# GPS_lure.net
KiCad netlist of a schematic drawn in EAGLE
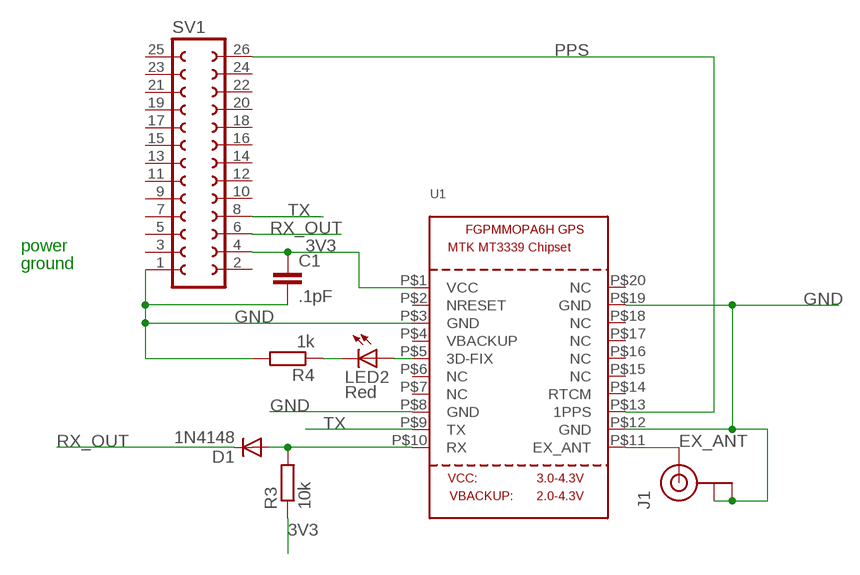
[diagram p0: schematic, sheet 1]

(export (version "E")
  (design (tool "Eeschema 10.0.6"))
  (components
    (comp (ref "C1")
      (value ".1pF")
      (footprint "eagle-import:C0805")
      (libsource (lib "eagle-import") (part "C-EUC0805"))
    )
    (comp (ref "D1")
      (value "1N4148")
      (footprint "eagle-import:SOD123")
      (libsource (lib "eagle-import") (part "DIODE-SOD123"))
    )
    (comp (ref "J1")
      (value "U.FL")
      (footprint "eagle-import:U.FL")
      (libsource (lib "eagle-import") (part "U.FL"))
    )
    (comp (ref "LED2")
      (value "Red")
      (footprint "eagle-import:CHIPLED_1206")
      (libsource (lib "eagle-import") (part "LEDCHIPLED_1206"))
    )
    (comp (ref "R3")
      (value "10k")
      (footprint "eagle-import:M1206")
      (libsource (lib "eagle-import") (part "R-EU_M1206"))
    )
    (comp (ref "R4")
      (value "1k")
      (footprint "eagle-import:M1206")
      (libsource (lib "eagle-import") (part "R-EU_M1206"))
    )
    (comp (ref "SV1")
      (value "FE13-2")
      (footprint "eagle-import:FE13-2")
      (libsource (lib "eagle-import") (part "FE13-2"))
    )
    (comp (ref "U1")
      (value "GPS_FGPMMOPA6H")
      (footprint "eagle-import:FGPMMOPA6H")
      (libsource (lib "eagle-import") (part "GPS_FGPMMOPA6H"))
    )
  )
  (nets
    (net (code "1") (name "/3V3") (class "Default")
      (node (ref "C1") (pin "1") (pinfunction "1_1") (pintype "passive"))
      (node (ref "R3") (pin "1") (pinfunction "1_1") (pintype "passive"))
      (node (ref "SV1") (pin "4") (pinfunction "4_4") (pintype "passive"))
      (node (ref "U1") (pin "P$1") (pinfunction "VCC_P$1") (pintype "bidirectional"))
    )
    (net (code "2") (name "/EX_ANT") (class "Default")
      (node (ref "J1") (pin "P$3") (pinfunction "SIGNAL_P$3") (pintype "bidirectional"))
      (node (ref "U1") (pin "P$11") (pinfunction "EX_ANT_P$11") (pintype "bidirectional"))
    )
    (net (code "3") (name "/GND") (class "Default")
      (node (ref "C1") (pin "2") (pinfunction "2_2") (pintype "passive"))
      (node (ref "J1") (pin "P$1") (pinfunction "GND_P$1") (pintype "bidirectional"))
      (node (ref "J1") (pin "P$2") (pinfunction "GND_P$2") (pintype "bidirectional"))
      (node (ref "R4") (pin "2") (pinfunction "2_2") (pintype "passive"))
      (node (ref "SV1") (pin "1") (pinfunction "1_1") (pintype "passive"))
      (node (ref "U1") (pin "P$12") (pinfunction "GND_P$12") (pintype "bidirectional"))
      (node (ref "U1") (pin "P$19") (pinfunction "GND_P$19") (pintype "bidirectional"))
      (node (ref "U1") (pin "P$3") (pinfunction "GND_P$3") (pintype "bidirectional"))
      (node (ref "U1") (pin "P$8") (pinfunction "GND_P$8") (pintype "bidirectional"))
    )
    (net (code "4") (name "/PPS") (class "Default")
      (node (ref "SV1") (pin "26") (pinfunction "26_26") (pintype "passive"))
      (node (ref "U1") (pin "P$13") (pinfunction "1PPS_P$13") (pintype "bidirectional"))
    )
    (net (code "5") (name "/RX_OUT") (class "Default")
      (node (ref "D1") (pin "C") (pinfunction "C_C") (pintype "passive"))
      (node (ref "SV1") (pin "6") (pinfunction "6_6") (pintype "passive"))
    )
    (net (code "6") (name "/TX") (class "Default")
      (node (ref "SV1") (pin "8") (pinfunction "8_8") (pintype "passive"))
      (node (ref "U1") (pin "P$9") (pinfunction "TX_P$9") (pintype "bidirectional"))
    )
    (net (code "7") (name "Net-(LED2-PadC)") (class "Default")
      (node (ref "LED2") (pin "C") (pinfunction "C_C") (pintype "passive"))
      (node (ref "R4") (pin "1") (pinfunction "1_1") (pintype "passive"))
    )
    (net (code "8") (name "Net-(U1-3D-FIX)") (class "Default")
      (node (ref "LED2") (pin "A") (pinfunction "A_A") (pintype "passive"))
      (node (ref "U1") (pin "P$5") (pinfunction "3D-FIX_P$5") (pintype "bidirectional"))
    )
    (net (code "9") (name "Net-(U1-RX)") (class "Default")
      (node (ref "D1") (pin "A") (pinfunction "A_A") (pintype "passive"))
      (node (ref "R3") (pin "2") (pinfunction "2_2") (pintype "passive"))
      (node (ref "U1") (pin "P$10") (pinfunction "RX_P$10") (pintype "bidirectional"))
    )
    (net (code "10") (name "unconnected-(SV1-Pad2)") (class "Default")
      (node (ref "SV1") (pin "2") (pinfunction "2_2") (pintype "passive"))
    )
    (net (code "11") (name "unconnected-(SV1-Pad3)") (class "Default")
      (node (ref "SV1") (pin "3") (pinfunction "3_3") (pintype "passive"))
    )
    (net (code "12") (name "unconnected-(SV1-Pad5)") (class "Default")
      (node (ref "SV1") (pin "5") (pinfunction "5_5") (pintype "passive"))
    )
    (net (code "13") (name "unconnected-(SV1-Pad7)") (class "Default")
      (node (ref "SV1") (pin "7") (pinfunction "7_7") (pintype "passive"))
    )
    (net (code "14") (name "unconnected-(SV1-Pad9)") (class "Default")
      (node (ref "SV1") (pin "9") (pinfunction "9_9") (pintype "passive"))
    )
    (net (code "15") (name "unconnected-(SV1-Pad10)") (class "Default")
      (node (ref "SV1") (pin "10") (pinfunction "10_10") (pintype "passive"))
    )
    (net (code "16") (name "unconnected-(SV1-Pad11)") (class "Default")
      (node (ref "SV1") (pin "11") (pinfunction "11_11") (pintype "passive"))
    )
    (net (code "17") (name "unconnected-(SV1-Pad12)") (class "Default")
      (node (ref "SV1") (pin "12") (pinfunction "12_12") (pintype "passive"))
    )
    (net (code "18") (name "unconnected-(SV1-Pad13)") (class "Default")
      (node (ref "SV1") (pin "13") (pinfunction "13_13") (pintype "passive"))
    )
    (net (code "19") (name "unconnected-(SV1-Pad14)") (class "Default")
      (node (ref "SV1") (pin "14") (pinfunction "14_14") (pintype "passive"))
    )
    (net (code "20") (name "unconnected-(SV1-Pad15)") (class "Default")
      (node (ref "SV1") (pin "15") (pinfunction "15_15") (pintype "passive"))
    )
    (net (code "21") (name "unconnected-(SV1-Pad16)") (class "Default")
      (node (ref "SV1") (pin "16") (pinfunction "16_16") (pintype "passive"))
    )
    (net (code "22") (name "unconnected-(SV1-Pad17)") (class "Default")
      (node (ref "SV1") (pin "17") (pinfunction "17_17") (pintype "passive"))
    )
    (net (code "23") (name "unconnected-(SV1-Pad18)") (class "Default")
      (node (ref "SV1") (pin "18") (pinfunction "18_18") (pintype "passive"))
    )
    (net (code "24") (name "unconnected-(SV1-Pad19)") (class "Default")
      (node (ref "SV1") (pin "19") (pinfunction "19_19") (pintype "passive"))
    )
    (net (code "25") (name "unconnected-(SV1-Pad20)") (class "Default")
      (node (ref "SV1") (pin "20") (pinfunction "20_20") (pintype "passive"))
    )
    (net (code "26") (name "unconnected-(SV1-Pad21)") (class "Default")
      (node (ref "SV1") (pin "21") (pinfunction "21_21") (pintype "passive"))
    )
    (net (code "27") (name "unconnected-(SV1-Pad22)") (class "Default")
      (node (ref "SV1") (pin "22") (pinfunction "22_22") (pintype "passive"))
    )
    (net (code "28") (name "unconnected-(SV1-Pad23)") (class "Default")
      (node (ref "SV1") (pin "23") (pinfunction "23_23") (pintype "passive"))
    )
    (net (code "29") (name "unconnected-(SV1-Pad24)") (class "Default")
      (node (ref "SV1") (pin "24") (pinfunction "24_24") (pintype "passive"))
    )
    (net (code "30") (name "unconnected-(SV1-Pad25)") (class "Default")
      (node (ref "SV1") (pin "25") (pinfunction "25_25") (pintype "passive"))
    )
    (net (code "31") (name "unconnected-(U1-NC-PadP$6)") (class "Default")
      (node (ref "U1") (pin "P$6") (pinfunction "NC_P$6") (pintype "bidirectional"))
    )
    (net (code "32") (name "unconnected-(U1-NC-PadP$7)") (class "Default")
      (node (ref "U1") (pin "P$7") (pinfunction "NC_P$7") (pintype "bidirectional"))
    )
    (net (code "33") (name "unconnected-(U1-NC-PadP$15)") (class "Default")
      (node (ref "U1") (pin "P$15") (pinfunction "NC_P$15") (pintype "bidirectional"))
    )
    (net (code "34") (name "unconnected-(U1-NC-PadP$16)") (class "Default")
      (node (ref "U1") (pin "P$16") (pinfunction "NC_P$16") (pintype "bidirectional"))
    )
    (net (code "35") (name "unconnected-(U1-NC-PadP$17)") (class "Default")
      (node (ref "U1") (pin "P$17") (pinfunction "NC_P$17") (pintype "bidirectional"))
    )
    (net (code "36") (name "unconnected-(U1-NC-PadP$18)") (class "Default")
      (node (ref "U1") (pin "P$18") (pinfunction "NC_P$18") (pintype "bidirectional"))
    )
    (net (code "37") (name "unconnected-(U1-NC-PadP$20)") (class "Default")
      (node (ref "U1") (pin "P$20") (pinfunction "NC_P$20") (pintype "bidirectional"))
    )
    (net (code "38") (name "unconnected-(U1-NRESET-PadP$2)") (class "Default")
      (node (ref "U1") (pin "P$2") (pinfunction "NRESET_P$2") (pintype "bidirectional"))
    )
    (net (code "39") (name "unconnected-(U1-RTCM-PadP$14)") (class "Default")
      (node (ref "U1") (pin "P$14") (pinfunction "RTCM_P$14") (pintype "bidirectional"))
    )
    (net (code "40") (name "unconnected-(U1-VBACKUP-PadP$4)") (class "Default")
      (node (ref "U1") (pin "P$4") (pinfunction "VBACKUP_P$4") (pintype "bidirectional"))
    )
  )
)
